# MXC01_v1_1.net
KiCad netlist of a schematic drawn in EAGLE
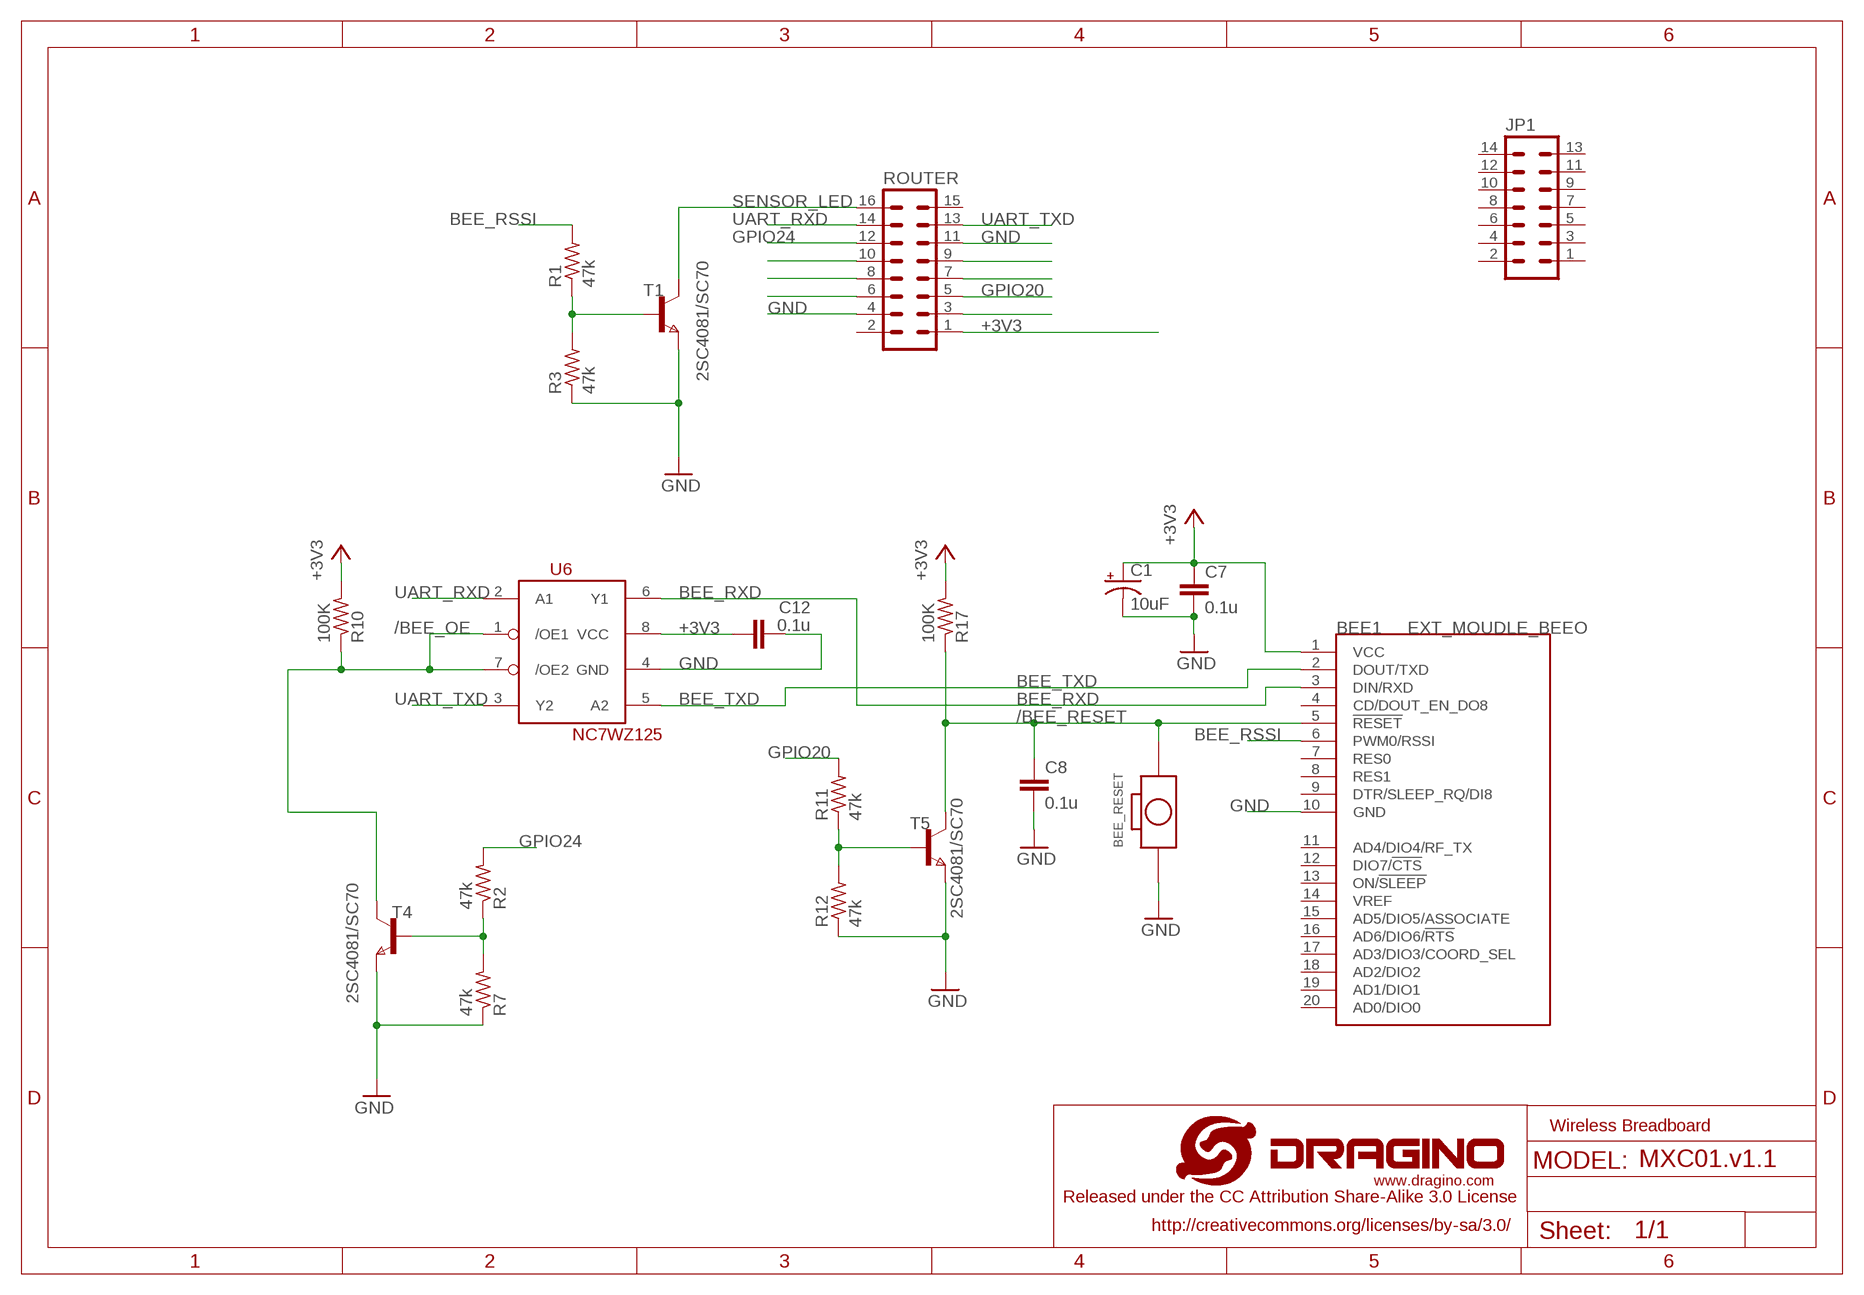
[diagram p0: schematic, sheet 1]

(export (version "E")
  (design (tool "Eeschema 10.0.6"))
  (components
    (comp (ref "BEE1")
      (value "EXT_MOUDLE_BEEO")
      (footprint "eagle-import:EXT_MOUDLE_BEE")
      (libsource (lib "eagle-import") (part "EXT_MOUDLE_BEEO"))
    )
    (comp (ref "BEE_RESET")
      (value "CPT_SMD_BOTTON_1_SMD")
      (footprint "eagle-import:CPT_SMD_BOTTON_1")
      (libsource (lib "eagle-import") (part "CPT_SMD_BOTTON_1_SMD"))
    )
    (comp (ref "C1")
      (value "10uF")
      (footprint "eagle-import:SMC_A")
      (libsource (lib "eagle-import") (part "CPOL-USSMCA"))
    )
    (comp (ref "C7")
      (value "0.1u")
      (footprint "eagle-import:C0402")
      (libsource (lib "eagle-import") (part "C-EUC0402"))
    )
    (comp (ref "C8")
      (value "0.1u")
      (footprint "eagle-import:C0402")
      (libsource (lib "eagle-import") (part "C-EUC0402"))
    )
    (comp (ref "C12")
      (value "0.1u")
      (footprint "eagle-import:C0402")
      (libsource (lib "eagle-import") (part "C-EUC0402"))
    )
    (comp (ref "JP1")
      (value "MA07-2")
      (footprint "eagle-import:MA07-2")
      (libsource (lib "eagle-import") (part "MA07-2"))
    )
    (comp (ref "R1")
      (value "47k")
      (footprint "eagle-import:R0402")
      (libsource (lib "eagle-import") (part "R-US_R0402"))
    )
    (comp (ref "R2")
      (value "47k")
      (footprint "eagle-import:R0402")
      (libsource (lib "eagle-import") (part "R-US_R0402"))
    )
    (comp (ref "R3")
      (value "47k")
      (footprint "eagle-import:R0402")
      (libsource (lib "eagle-import") (part "R-US_R0402"))
    )
    (comp (ref "R7")
      (value "47k")
      (footprint "eagle-import:R0402")
      (libsource (lib "eagle-import") (part "R-US_R0402"))
    )
    (comp (ref "R10")
      (value "100K")
      (footprint "eagle-import:R0402")
      (libsource (lib "eagle-import") (part "R-US_R0402"))
    )
    (comp (ref "R11")
      (value "47k")
      (footprint "eagle-import:R0402")
      (libsource (lib "eagle-import") (part "R-US_R0402"))
    )
    (comp (ref "R12")
      (value "47k")
      (footprint "eagle-import:R0402")
      (libsource (lib "eagle-import") (part "R-US_R0402"))
    )
    (comp (ref "R17")
      (value "100K")
      (footprint "eagle-import:R0402")
      (libsource (lib "eagle-import") (part "R-US_R0402"))
    )
    (comp (ref "ROUTER")
      (value "MA08-2")
      (footprint "eagle-import:MA08-2")
      (libsource (lib "eagle-import") (part "MA08-2"))
    )
    (comp (ref "T1")
      (value "2SC4081/SC70")
      (footprint "eagle-import:SOT323")
      (fields (field (name "MPN") "DSS4160U-7"))
      (libsource (lib "eagle-import") (part "NPNSOT323"))
    )
    (comp (ref "T4")
      (value "2SC4081/SC70")
      (footprint "eagle-import:SOT323")
      (fields (field (name "MPN") "DSS4160U-7"))
      (libsource (lib "eagle-import") (part "NPNSOT323"))
    )
    (comp (ref "T5")
      (value "2SC4081/SC70")
      (footprint "eagle-import:SOT323")
      (fields (field (name "MPN") "DSS4160U-7"))
      (libsource (lib "eagle-import") (part "NPNSOT323"))
    )
    (comp (ref "U$1")
      (value "LOGO-NEW")
      (footprint "eagle-import:LOGO-SILK-NEW")
      (libsource (lib "eagle-import") (part "LOGO-NEW"))
    )
    (comp (ref "U6")
      (value "NC7WZ125")
      (footprint "eagle-import:US8")
      (libsource (lib "eagle-import") (part "NC7WZ125"))
    )
  )
  (nets
    (net (code "1") (name "+3V3") (class "Default")
      (node (ref "BEE1") (pin "1") (pinfunction "VCC_1") (pintype "bidirectional"))
      (node (ref "C1") (pin "+") (pinfunction "+_+") (pintype "passive"))
      (node (ref "C12") (pin "1") (pinfunction "1_1") (pintype "passive"))
      (node (ref "C7") (pin "1") (pinfunction "1_1") (pintype "passive"))
      (node (ref "R10") (pin "2") (pinfunction "2_2") (pintype "passive"))
      (node (ref "R17") (pin "2") (pinfunction "2_2") (pintype "passive"))
      (node (ref "ROUTER") (pin "1") (pinfunction "1_1") (pintype "passive"))
      (node (ref "U6") (pin "8") (pinfunction "VCC_8") (pintype "power_in"))
    )
    (net (code "2") (name "/BEE_RSSI") (class "Default")
      (node (ref "BEE1") (pin "6") (pinfunction "PWM0/RSSI_6") (pintype "bidirectional"))
      (node (ref "R1") (pin "2") (pinfunction "2_2") (pintype "passive"))
    )
    (net (code "3") (name "/BEE_RXD") (class "Default")
      (node (ref "BEE1") (pin "3") (pinfunction "DIN/RXD_3") (pintype "bidirectional"))
      (node (ref "U6") (pin "6") (pinfunction "Y1_6") (pintype "output"))
    )
    (net (code "4") (name "/BEE_TXD") (class "Default")
      (node (ref "BEE1") (pin "2") (pinfunction "DOUT/TXD_2") (pintype "bidirectional"))
      (node (ref "U6") (pin "5") (pinfunction "A2_5") (pintype "input"))
    )
    (net (code "5") (name "/GPIO20") (class "Default")
      (node (ref "R11") (pin "2") (pinfunction "2_2") (pintype "passive"))
      (node (ref "ROUTER") (pin "5") (pinfunction "5_5") (pintype "passive"))
    )
    (net (code "6") (name "/GPIO24") (class "Default")
      (node (ref "R2") (pin "2") (pinfunction "2_2") (pintype "passive"))
      (node (ref "ROUTER") (pin "12") (pinfunction "12_12") (pintype "passive"))
    )
    (net (code "7") (name "/SENSOR_LED") (class "Default")
      (node (ref "ROUTER") (pin "16") (pinfunction "16_16") (pintype "passive"))
      (node (ref "T1") (pin "1") (pinfunction "C_1") (pintype "passive"))
    )
    (net (code "8") (name "/UART_RXD") (class "Default")
      (node (ref "ROUTER") (pin "14") (pinfunction "14_14") (pintype "passive"))
      (node (ref "U6") (pin "2") (pinfunction "A1_2") (pintype "input"))
    )
    (net (code "9") (name "/UART_TXD") (class "Default")
      (node (ref "ROUTER") (pin "13") (pinfunction "13_13") (pintype "passive"))
      (node (ref "U6") (pin "3") (pinfunction "Y2_3") (pintype "output"))
    )
    (net (code "10") (name "/{slash}BEE_OE") (class "Default")
      (node (ref "R10") (pin "1") (pinfunction "1_1") (pintype "passive"))
      (node (ref "T4") (pin "1") (pinfunction "C_1") (pintype "passive"))
      (node (ref "U6") (pin "1") (pinfunction "/OE1_1") (pintype "input"))
      (node (ref "U6") (pin "7") (pinfunction "/OE2_7") (pintype "input"))
    )
    (net (code "11") (name "/{slash}BEE_RESET") (class "Default")
      (node (ref "BEE1") (pin "5") (pinfunction "~{RESET}_5") (pintype "bidirectional"))
      (node (ref "BEE_RESET") (pin "P$2") (pinfunction "2_P$2") (pintype "bidirectional"))
      (node (ref "C8") (pin "1") (pinfunction "1_1") (pintype "passive"))
      (node (ref "R17") (pin "1") (pinfunction "1_1") (pintype "passive"))
      (node (ref "T5") (pin "1") (pinfunction "C_1") (pintype "passive"))
    )
    (net (code "12") (name "GND") (class "Default")
      (node (ref "BEE1") (pin "10") (pinfunction "GND_10") (pintype "bidirectional"))
      (node (ref "BEE_RESET") (pin "1") (pinfunction "1_1") (pintype "bidirectional"))
      (node (ref "C1") (pin "-") (pinfunction "-_-") (pintype "passive"))
      (node (ref "C12") (pin "2") (pinfunction "2_2") (pintype "passive"))
      (node (ref "C7") (pin "2") (pinfunction "2_2") (pintype "passive"))
      (node (ref "C8") (pin "2") (pinfunction "2_2") (pintype "passive"))
      (node (ref "R12") (pin "1") (pinfunction "1_1") (pintype "passive"))
      (node (ref "R3") (pin "1") (pinfunction "1_1") (pintype "passive"))
      (node (ref "R7") (pin "1") (pinfunction "1_1") (pintype "passive"))
      (node (ref "ROUTER") (pin "11") (pinfunction "11_11") (pintype "passive"))
      (node (ref "ROUTER") (pin "4") (pinfunction "4_4") (pintype "passive"))
      (node (ref "T1") (pin "3") (pinfunction "E_3") (pintype "passive"))
      (node (ref "T4") (pin "3") (pinfunction "E_3") (pintype "passive"))
      (node (ref "T5") (pin "3") (pinfunction "E_3") (pintype "passive"))
      (node (ref "U6") (pin "4") (pinfunction "GND_4") (pintype "power_in"))
    )
    (net (code "13") (name "Net-(T1-B)") (class "Default")
      (node (ref "R1") (pin "1") (pinfunction "1_1") (pintype "passive"))
      (node (ref "R3") (pin "2") (pinfunction "2_2") (pintype "passive"))
      (node (ref "T1") (pin "2") (pinfunction "B_2") (pintype "passive"))
    )
    (net (code "14") (name "Net-(T4-B)") (class "Default")
      (node (ref "R2") (pin "1") (pinfunction "1_1") (pintype "passive"))
      (node (ref "R7") (pin "2") (pinfunction "2_2") (pintype "passive"))
      (node (ref "T4") (pin "2") (pinfunction "B_2") (pintype "passive"))
    )
    (net (code "15") (name "Net-(T5-B)") (class "Default")
      (node (ref "R11") (pin "1") (pinfunction "1_1") (pintype "passive"))
      (node (ref "R12") (pin "2") (pinfunction "2_2") (pintype "passive"))
      (node (ref "T5") (pin "2") (pinfunction "B_2") (pintype "passive"))
    )
    (net (code "16") (name "unconnected-(BEE1-AD0{slash}DIO0-Pad20)") (class "Default")
      (node (ref "BEE1") (pin "20") (pinfunction "AD0/DIO0_20") (pintype "bidirectional"))
    )
    (net (code "17") (name "unconnected-(BEE1-AD1{slash}DIO1-Pad19)") (class "Default")
      (node (ref "BEE1") (pin "19") (pinfunction "AD1/DIO1_19") (pintype "bidirectional"))
    )
    (net (code "18") (name "unconnected-(BEE1-AD2{slash}DIO2-Pad18)") (class "Default")
      (node (ref "BEE1") (pin "18") (pinfunction "AD2/DIO2_18") (pintype "bidirectional"))
    )
    (net (code "19") (name "unconnected-(BEE1-AD3{slash}DIO3{slash}COORD_SEL-Pad17)") (class "Default")
      (node (ref "BEE1") (pin "17") (pinfunction "AD3/DIO3/COORD_SEL_17") (pintype "bidirectional"))
    )
    (net (code "20") (name "unconnected-(BEE1-AD4{slash}DIO4{slash}RF_TX-Pad11)") (class "Default")
      (node (ref "BEE1") (pin "11") (pinfunction "AD4/DIO4/RF_TX_11") (pintype "bidirectional"))
    )
    (net (code "21") (name "unconnected-(BEE1-AD5{slash}DIO5{slash}ASSOCIATE-Pad15)") (class "Default")
      (node (ref "BEE1") (pin "15") (pinfunction "AD5/DIO5/ASSOCIATE_15") (pintype "bidirectional"))
    )
    (net (code "22") (name "unconnected-(BEE1-AD6{slash}DIO6{slash}~{RTS}-Pad16)") (class "Default")
      (node (ref "BEE1") (pin "16") (pinfunction "AD6/DIO6/~{RTS}_16") (pintype "bidirectional"))
    )
    (net (code "23") (name "unconnected-(BEE1-CD{slash}DOUT_EN_DO8-Pad4)") (class "Default")
      (node (ref "BEE1") (pin "4") (pinfunction "CD/DOUT_EN_DO8_4") (pintype "bidirectional"))
    )
    (net (code "24") (name "unconnected-(BEE1-DIO7{slash}~{CTS}-Pad12)") (class "Default")
      (node (ref "BEE1") (pin "12") (pinfunction "DIO7/~{CTS}_12") (pintype "bidirectional"))
    )
    (net (code "25") (name "unconnected-(BEE1-DTR{slash}SLEEP_RQ{slash}DI8-Pad9)") (class "Default")
      (node (ref "BEE1") (pin "9") (pinfunction "DTR/SLEEP_RQ/DI8_9") (pintype "bidirectional"))
    )
    (net (code "26") (name "unconnected-(BEE1-ON{slash}~{SLEEP}-Pad13)") (class "Default")
      (node (ref "BEE1") (pin "13") (pinfunction "ON/~{SLEEP}_13") (pintype "bidirectional"))
    )
    (net (code "27") (name "unconnected-(BEE1-RES0-Pad7)") (class "Default")
      (node (ref "BEE1") (pin "7") (pinfunction "RES0_7") (pintype "bidirectional"))
    )
    (net (code "28") (name "unconnected-(BEE1-RES1-Pad8)") (class "Default")
      (node (ref "BEE1") (pin "8") (pinfunction "RES1_8") (pintype "bidirectional"))
    )
    (net (code "29") (name "unconnected-(BEE1-VREF-Pad14)") (class "Default")
      (node (ref "BEE1") (pin "14") (pinfunction "VREF_14") (pintype "bidirectional"))
    )
    (net (code "30") (name "unconnected-(JP1-Pad1)") (class "Default")
      (node (ref "JP1") (pin "1") (pinfunction "1_1") (pintype "passive"))
    )
    (net (code "31") (name "unconnected-(JP1-Pad2)") (class "Default")
      (node (ref "JP1") (pin "2") (pinfunction "2_2") (pintype "passive"))
    )
    (net (code "32") (name "unconnected-(JP1-Pad3)") (class "Default")
      (node (ref "JP1") (pin "3") (pinfunction "3_3") (pintype "passive"))
    )
    (net (code "33") (name "unconnected-(JP1-Pad4)") (class "Default")
      (node (ref "JP1") (pin "4") (pinfunction "4_4") (pintype "passive"))
    )
    (net (code "34") (name "unconnected-(JP1-Pad5)") (class "Default")
      (node (ref "JP1") (pin "5") (pinfunction "5_5") (pintype "passive"))
    )
    (net (code "35") (name "unconnected-(JP1-Pad6)") (class "Default")
      (node (ref "JP1") (pin "6") (pinfunction "6_6") (pintype "passive"))
    )
    (net (code "36") (name "unconnected-(JP1-Pad7)") (class "Default")
      (node (ref "JP1") (pin "7") (pinfunction "7_7") (pintype "passive"))
    )
    (net (code "37") (name "unconnected-(JP1-Pad8)") (class "Default")
      (node (ref "JP1") (pin "8") (pinfunction "8_8") (pintype "passive"))
    )
    (net (code "38") (name "unconnected-(JP1-Pad9)") (class "Default")
      (node (ref "JP1") (pin "9") (pinfunction "9_9") (pintype "passive"))
    )
    (net (code "39") (name "unconnected-(JP1-Pad10)") (class "Default")
      (node (ref "JP1") (pin "10") (pinfunction "10_10") (pintype "passive"))
    )
    (net (code "40") (name "unconnected-(JP1-Pad11)") (class "Default")
      (node (ref "JP1") (pin "11") (pinfunction "11_11") (pintype "passive"))
    )
    (net (code "41") (name "unconnected-(JP1-Pad12)") (class "Default")
      (node (ref "JP1") (pin "12") (pinfunction "12_12") (pintype "passive"))
    )
    (net (code "42") (name "unconnected-(JP1-Pad13)") (class "Default")
      (node (ref "JP1") (pin "13") (pinfunction "13_13") (pintype "passive"))
    )
    (net (code "43") (name "unconnected-(JP1-Pad14)") (class "Default")
      (node (ref "JP1") (pin "14") (pinfunction "14_14") (pintype "passive"))
    )
    (net (code "44") (name "unconnected-(ROUTER-Pad2)") (class "Default")
      (node (ref "ROUTER") (pin "2") (pinfunction "2_2") (pintype "passive"))
    )
    (net (code "45") (name "unconnected-(ROUTER-Pad3)") (class "Default")
      (node (ref "ROUTER") (pin "3") (pinfunction "3_3") (pintype "passive"))
    )
    (net (code "46") (name "unconnected-(ROUTER-Pad6)") (class "Default")
      (node (ref "ROUTER") (pin "6") (pinfunction "6_6") (pintype "passive"))
    )
    (net (code "47") (name "unconnected-(ROUTER-Pad7)") (class "Default")
      (node (ref "ROUTER") (pin "7") (pinfunction "7_7") (pintype "passive"))
    )
    (net (code "48") (name "unconnected-(ROUTER-Pad8)") (class "Default")
      (node (ref "ROUTER") (pin "8") (pinfunction "8_8") (pintype "passive"))
    )
    (net (code "49") (name "unconnected-(ROUTER-Pad9)") (class "Default")
      (node (ref "ROUTER") (pin "9") (pinfunction "9_9") (pintype "passive"))
    )
    (net (code "50") (name "unconnected-(ROUTER-Pad10)") (class "Default")
      (node (ref "ROUTER") (pin "10") (pinfunction "10_10") (pintype "passive"))
    )
    (net (code "51") (name "unconnected-(ROUTER-Pad15)") (class "Default")
      (node (ref "ROUTER") (pin "15") (pinfunction "15_15") (pintype "passive"))
    )
  )
)
